# Salmon.net
KiCad netlist of a schematic drawn in Altium Designer
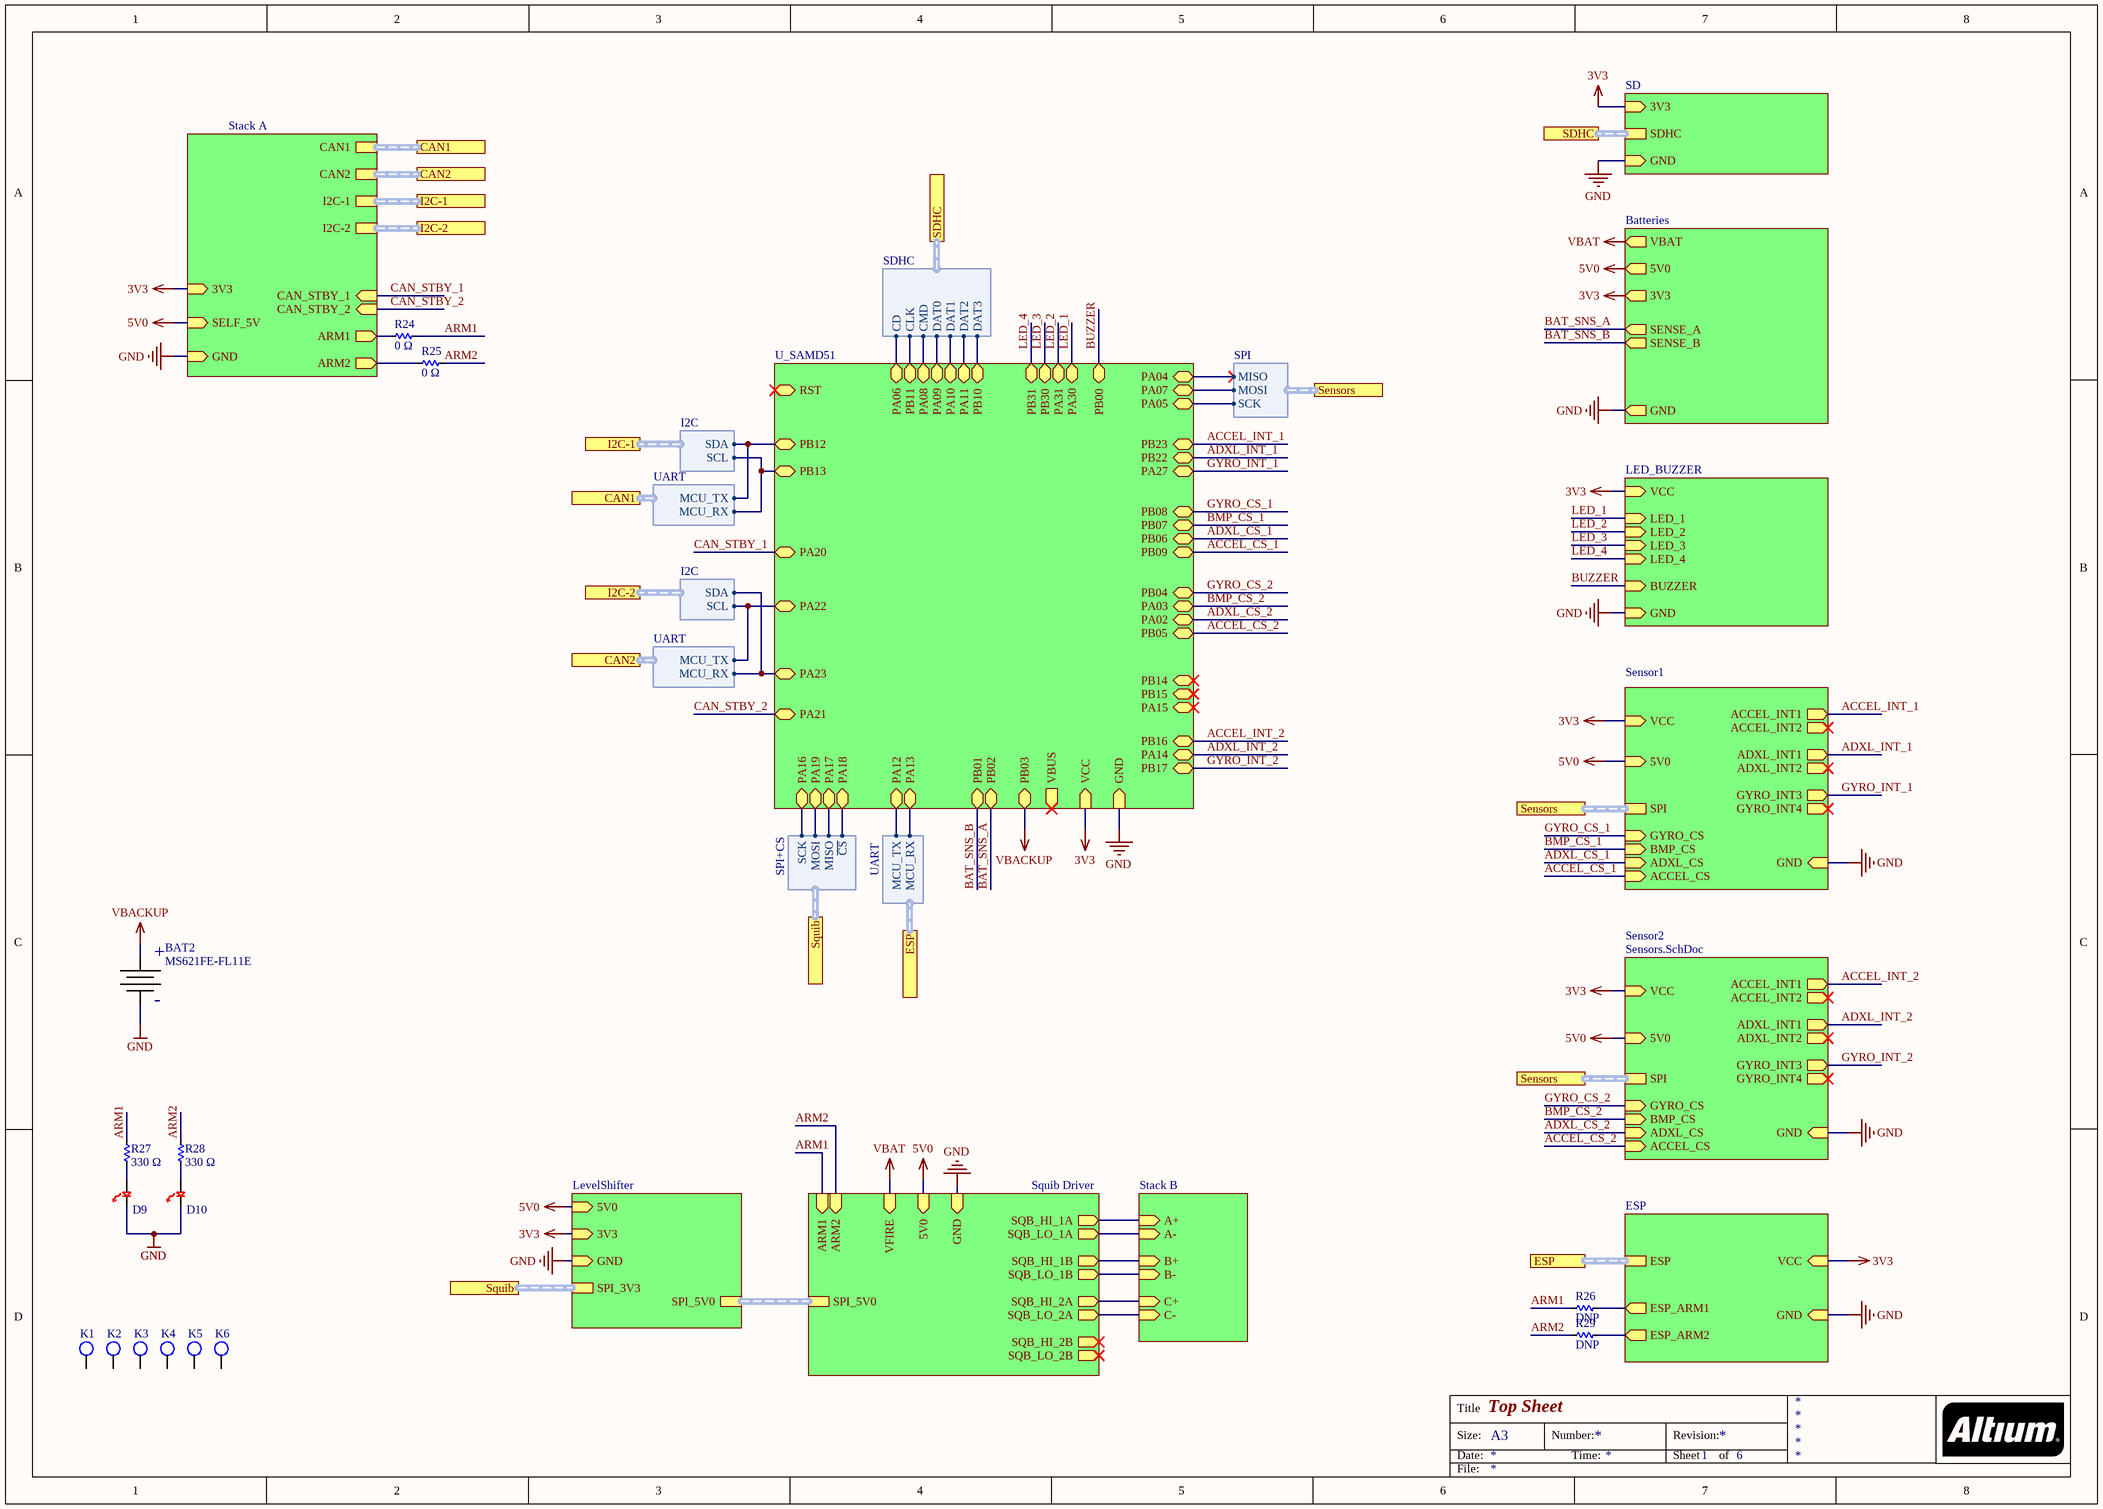
[diagram p0: Salmon.SchDoc]

(export (version "E")
  (design (tool "Eeschema 10.0.6"))
  (components
    (comp (ref "BAT2")
      (value "MS621FE-FL11E")
      (footprint "BATT_COINCELL_RECHARGEABLE")
      (description "MS621FE RECHARGEABLE COIN CELL BACKUP")
      (fields (field (name "MANUFACTURER") "Seiko Instruments"))
      (libsource (lib "SSI") (part "BAT_MS621FE"))
    )
    (comp (ref "D9")
      (value "RED")
      (footprint "0805_Diode")
      (description "LED 0805 RED 20MA")
      (fields
        (field (name "MANUFACTURER") "OSRAM Opto Semiconductors Inc")
        (field (name "MANUFACTURER PART NUMBER") "LH R974-LP-1")
      )
      (libsource (lib "SSI") (part "LED_LY974"))
    )
    (comp (ref "D10")
      (value "RED")
      (footprint "0805_Diode")
      (description "LED 0805 RED 20MA")
      (fields
        (field (name "MANUFACTURER") "OSRAM Opto Semiconductors Inc")
        (field (name "MANUFACTURER PART NUMBER") "LH R974-LP-1")
      )
      (libsource (lib "SSI") (part "LED_LY974"))
    )
    (comp (ref "K1")
      (value "92985A610")
      (footprint "#4_PRESSFIT_FOOT_1/4")
      (description "Press-Fit Unthreaded Spacers, 7/32\" OD, 1/8\" Long")
      (libsource (lib "mechanical") (part "#4_PRESSFIT_MOUNTING_FOOT"))
    )
    (comp (ref "K2")
      (value "92985A610")
      (footprint "#4_PRESSFIT_FOOT_1/4")
      (description "Press-Fit Unthreaded Spacers, 7/32\" OD, 1/8\" Long")
      (libsource (lib "mechanical") (part "#4_PRESSFIT_MOUNTING_FOOT"))
    )
    (comp (ref "K3")
      (value "92985A610")
      (footprint "#4_PRESSFIT_FOOT_1/4")
      (description "Press-Fit Unthreaded Spacers, 7/32\" OD, 1/8\" Long")
      (libsource (lib "mechanical") (part "#4_PRESSFIT_MOUNTING_FOOT"))
    )
    (comp (ref "K4")
      (value "92985A610")
      (footprint "#4_PRESSFIT_FOOT_1/4")
      (description "Press-Fit Unthreaded Spacers, 7/32\" OD, 1/8\" Long")
      (libsource (lib "mechanical") (part "#4_PRESSFIT_MOUNTING_FOOT"))
    )
    (comp (ref "K5")
      (value "92985A610")
      (footprint "#4_PRESSFIT_FOOT_1/4")
      (description "Press-Fit Unthreaded Spacers, 7/32\" OD, 1/8\" Long")
      (libsource (lib "mechanical") (part "#4_PRESSFIT_MOUNTING_FOOT"))
    )
    (comp (ref "K6")
      (value "92985A610")
      (footprint "#4_PRESSFIT_FOOT_1/4")
      (description "Press-Fit Unthreaded Spacers, 7/32\" OD, 1/8\" Long")
      (libsource (lib "mechanical") (part "#4_PRESSFIT_MOUNTING_FOOT"))
    )
    (comp (ref "R24")
      (value "__template_resistor")
      (footprint "R0603")
      (fields
        (field (name "RESISTANCE") "0 Ω")
        (field (name "MANUFACTURER PART NUMBER") "RC0603FR-070RL")
        (field (name "MANUFACTURER") "Yageo")
        (field (name "TOLERANCE") "Jumper")
      )
      (libsource (lib "passives") (part "__template_resistor"))
    )
    (comp (ref "R25")
      (value "__template_resistor")
      (footprint "R0603")
      (fields
        (field (name "RESISTANCE") "0 Ω")
        (field (name "MANUFACTURER PART NUMBER") "RC0603FR-070RL")
        (field (name "MANUFACTURER") "Yageo")
        (field (name "TOLERANCE") "Jumper")
      )
      (libsource (lib "passives") (part "__template_resistor"))
    )
    (comp (ref "R26")
      (value "__template_resistor")
      (footprint "R0603")
      (fields (field (name "RESISTANCE") "DNP"))
      (libsource (lib "passives") (part "__template_resistor"))
    )
    (comp (ref "R27")
      (value "__template_resistor")
      (footprint "R0603")
      (fields
        (field (name "RESISTANCE") "330 Ω")
        (field (name "MANUFACTURER PART NUMBER") "RC0603FR-07330RL")
        (field (name "MANUFACTURER") "Yageo")
        (field (name "TOLERANCE") "±1%")
      )
      (libsource (lib "passives") (part "__template_resistor"))
    )
    (comp (ref "R28")
      (value "__template_resistor")
      (footprint "R0603")
      (fields
        (field (name "RESISTANCE") "330 Ω")
        (field (name "MANUFACTURER PART NUMBER") "RC0603FR-07330RL")
        (field (name "MANUFACTURER") "Yageo")
        (field (name "TOLERANCE") "±1%")
      )
      (libsource (lib "passives") (part "__template_resistor"))
    )
    (comp (ref "R29")
      (value "__template_resistor")
      (footprint "R0603")
      (fields (field (name "RESISTANCE") "DNP"))
      (libsource (lib "passives") (part "__template_resistor"))
    )
  )
  (nets
    (net (code "17") (name "/ARM1") (class "Default")
      (node (ref "R24") (pin "2") (pintype "passive"))
      (node (ref "R26") (pin "1") (pintype "passive"))
      (node (ref "R27") (pin "2") (pintype "passive"))
    )
    (net (code "18") (name "/ARM1_1") (class "Default") (node (ref "R24") (pin "1") (pintype "passive")))
    (net (code "19") (name "/ARM2") (class "Default")
      (node (ref "R25") (pin "2") (pintype "passive"))
      (node (ref "R28") (pin "2") (pintype "passive"))
      (node (ref "R29") (pin "1") (pintype "passive"))
    )
    (net (code "20") (name "/ARM2_1") (class "Default") (node (ref "R25") (pin "1") (pintype "passive")))
    (net (code "28") (name "/ESP_ARM1") (class "Default") (node (ref "R26") (pin "2") (pintype "passive")))
    (net (code "29") (name "/ESP_ARM2") (class "Default") (node (ref "R29") (pin "2") (pintype "passive")))
    (net (code "82") (name "GND") (class "Default")
      (node (ref "BAT2") (pin "-") (pintype "passive"))
      (node (ref "D10") (pin "1") (pintype "passive"))
      (node (ref "D9") (pin "1") (pintype "passive"))
    )
    (net (code "83") (name "Net-(D9-Pad2)") (class "Default")
      (node (ref "D9") (pin "2") (pintype "passive"))
      (node (ref "R27") (pin "1") (pintype "passive"))
    )
    (net (code "84") (name "Net-(D10-Pad2)") (class "Default")
      (node (ref "D10") (pin "2") (pintype "passive"))
      (node (ref "R28") (pin "1") (pintype "passive"))
    )
    (net (code "85") (name "VBACKUP") (class "Default") (node (ref "BAT2") (pin "+") (pintype "passive")))
    (net (code "87") (name "unconnected-(K1-Pad1)") (class "Default")
      (node (ref "K1") (pin "1") (pinfunction "1_1") (pintype "passive"))
    )
    (net (code "88") (name "unconnected-(K2-Pad1)") (class "Default")
      (node (ref "K2") (pin "1") (pinfunction "1_1") (pintype "passive"))
    )
    (net (code "89") (name "unconnected-(K3-Pad1)") (class "Default")
      (node (ref "K3") (pin "1") (pinfunction "1_1") (pintype "passive"))
    )
    (net (code "90") (name "unconnected-(K4-Pad1)") (class "Default")
      (node (ref "K4") (pin "1") (pinfunction "1_1") (pintype "passive"))
    )
    (net (code "91") (name "unconnected-(K5-Pad1)") (class "Default")
      (node (ref "K5") (pin "1") (pinfunction "1_1") (pintype "passive"))
    )
    (net (code "92") (name "unconnected-(K6-Pad1)") (class "Default")
      (node (ref "K6") (pin "1") (pinfunction "1_1") (pintype "passive"))
    )
  )
)
